# Button3x4S-4_Sch.net
KiCad netlist of a schematic drawn in Altium Designer
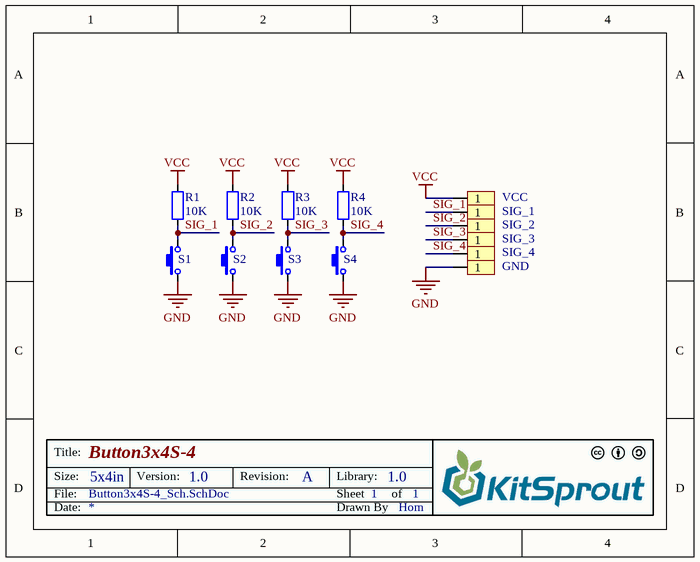
[diagram p0: Button3x4S-4_Sch.SchDoc]

(export (version "E")
  (design (tool "Eeschema 10.0.6"))
  (components
    (comp (ref "GND")
      (value "HDR-PAD_2.54")
      (footprint "PCB_ConnectorHDR:HDR-PAD_2.54")
      (description "Header")
      (libsource (lib "SCH_ConnectorHDR") (part "HDR-PAD_2.54"))
    )
    (comp (ref "R1")
      (value "10K")
      (footprint "PCB_PassiveRes:RES_0603")
      (description "Resistor")
      (fields (field (name "Comment") "Res_0603"))
      (libsource (lib "SCH_Passive") (part "Res_0603"))
    )
    (comp (ref "R2")
      (value "10K")
      (footprint "PCB_PassiveRes:RES_0603")
      (description "Resistor")
      (fields (field (name "Comment") "Res_0603"))
      (libsource (lib "SCH_Passive") (part "Res_0603"))
    )
    (comp (ref "R3")
      (value "10K")
      (footprint "PCB_PassiveRes:RES_0603")
      (description "Resistor")
      (fields (field (name "Comment") "Res_0603"))
      (libsource (lib "SCH_Passive") (part "Res_0603"))
    )
    (comp (ref "R4")
      (value "10K")
      (footprint "PCB_PassiveRes:RES_0603")
      (description "Resistor")
      (fields (field (name "Comment") "Res_0603"))
      (libsource (lib "SCH_Passive") (part "Res_0603"))
    )
    (comp (ref "S1")
      (value "ButtonTACT_3x4x2_180")
      (footprint "PCB_Switch:ButtonTACT_3x4x2_180H")
      (description "Button")
      (libsource (lib "SCH_Switch") (part "ButtonTACT_3x4x2_180"))
    )
    (comp (ref "S2")
      (value "ButtonTACT_3x4x2_180")
      (footprint "PCB_Switch:ButtonTACT_3x4x2_180H")
      (description "Button")
      (libsource (lib "SCH_Switch") (part "ButtonTACT_3x4x2_180"))
    )
    (comp (ref "S3")
      (value "ButtonTACT_3x4x2_180")
      (footprint "PCB_Switch:ButtonTACT_3x4x2_180H")
      (description "Button")
      (libsource (lib "SCH_Switch") (part "ButtonTACT_3x4x2_180"))
    )
    (comp (ref "S4")
      (value "ButtonTACT_3x4x2_180")
      (footprint "PCB_Switch:ButtonTACT_3x4x2_180H")
      (description "Button")
      (libsource (lib "SCH_Switch") (part "ButtonTACT_3x4x2_180"))
    )
    (comp (ref "SIG_1")
      (value "HDR-PAD_2.54")
      (footprint "PCB_ConnectorHDR:HDR-PAD_2.54")
      (description "Header")
      (libsource (lib "SCH_ConnectorHDR") (part "HDR-PAD_2.54"))
    )
    (comp (ref "SIG_2")
      (value "HDR-PAD_2.54")
      (footprint "PCB_ConnectorHDR:HDR-PAD_2.54")
      (description "Header")
      (libsource (lib "SCH_ConnectorHDR") (part "HDR-PAD_2.54"))
    )
    (comp (ref "SIG_3")
      (value "HDR-PAD_2.54")
      (footprint "PCB_ConnectorHDR:HDR-PAD_2.54")
      (description "Header")
      (libsource (lib "SCH_ConnectorHDR") (part "HDR-PAD_2.54"))
    )
    (comp (ref "SIG_4")
      (value "HDR-PAD_2.54")
      (footprint "PCB_ConnectorHDR:HDR-PAD_2.54")
      (description "Header")
      (libsource (lib "SCH_ConnectorHDR") (part "HDR-PAD_2.54"))
    )
    (comp (ref "VCC")
      (value "HDR-PAD_2.54")
      (footprint "PCB_ConnectorHDR:HDR-PAD_2.54")
      (description "Header")
      (libsource (lib "SCH_ConnectorHDR") (part "HDR-PAD_2.54"))
    )
  )
  (nets
    (net (code "1") (name "/SIG_1") (class "Default")
      (node (ref "R1") (pin "1") (pinfunction "1_1") (pintype "passive"))
      (node (ref "S1") (pin "2") (pinfunction "2_2") (pintype "passive"))
      (node (ref "SIG_1") (pin "1") (pinfunction "1_1") (pintype "passive"))
    )
    (net (code "2") (name "/SIG_2") (class "Default")
      (node (ref "R2") (pin "1") (pinfunction "1_1") (pintype "passive"))
      (node (ref "S2") (pin "2") (pinfunction "2_2") (pintype "passive"))
      (node (ref "SIG_2") (pin "1") (pinfunction "1_1") (pintype "passive"))
    )
    (net (code "3") (name "/SIG_3") (class "Default")
      (node (ref "R3") (pin "1") (pinfunction "1_1") (pintype "passive"))
      (node (ref "S3") (pin "2") (pinfunction "2_2") (pintype "passive"))
      (node (ref "SIG_3") (pin "1") (pinfunction "1_1") (pintype "passive"))
    )
    (net (code "4") (name "/SIG_4") (class "Default")
      (node (ref "R4") (pin "1") (pinfunction "1_1") (pintype "passive"))
      (node (ref "S4") (pin "2") (pinfunction "2_2") (pintype "passive"))
      (node (ref "SIG_4") (pin "1") (pinfunction "1_1") (pintype "passive"))
    )
    (net (code "5") (name "GND") (class "Default")
      (node (ref "GND") (pin "1") (pinfunction "1_1") (pintype "passive"))
      (node (ref "S1") (pin "1") (pinfunction "1_1") (pintype "passive"))
      (node (ref "S2") (pin "1") (pinfunction "1_1") (pintype "passive"))
      (node (ref "S3") (pin "1") (pinfunction "1_1") (pintype "passive"))
      (node (ref "S4") (pin "1") (pinfunction "1_1") (pintype "passive"))
    )
    (net (code "6") (name "VCC") (class "Default")
      (node (ref "R1") (pin "2") (pinfunction "2_2") (pintype "passive"))
      (node (ref "R2") (pin "2") (pinfunction "2_2") (pintype "passive"))
      (node (ref "R3") (pin "2") (pinfunction "2_2") (pintype "passive"))
      (node (ref "R4") (pin "2") (pinfunction "2_2") (pintype "passive"))
      (node (ref "VCC") (pin "1") (pinfunction "1_1") (pintype "passive"))
    )
  )
)
